# Signals.net
KiCad netlist of a schematic drawn in Altium Designer
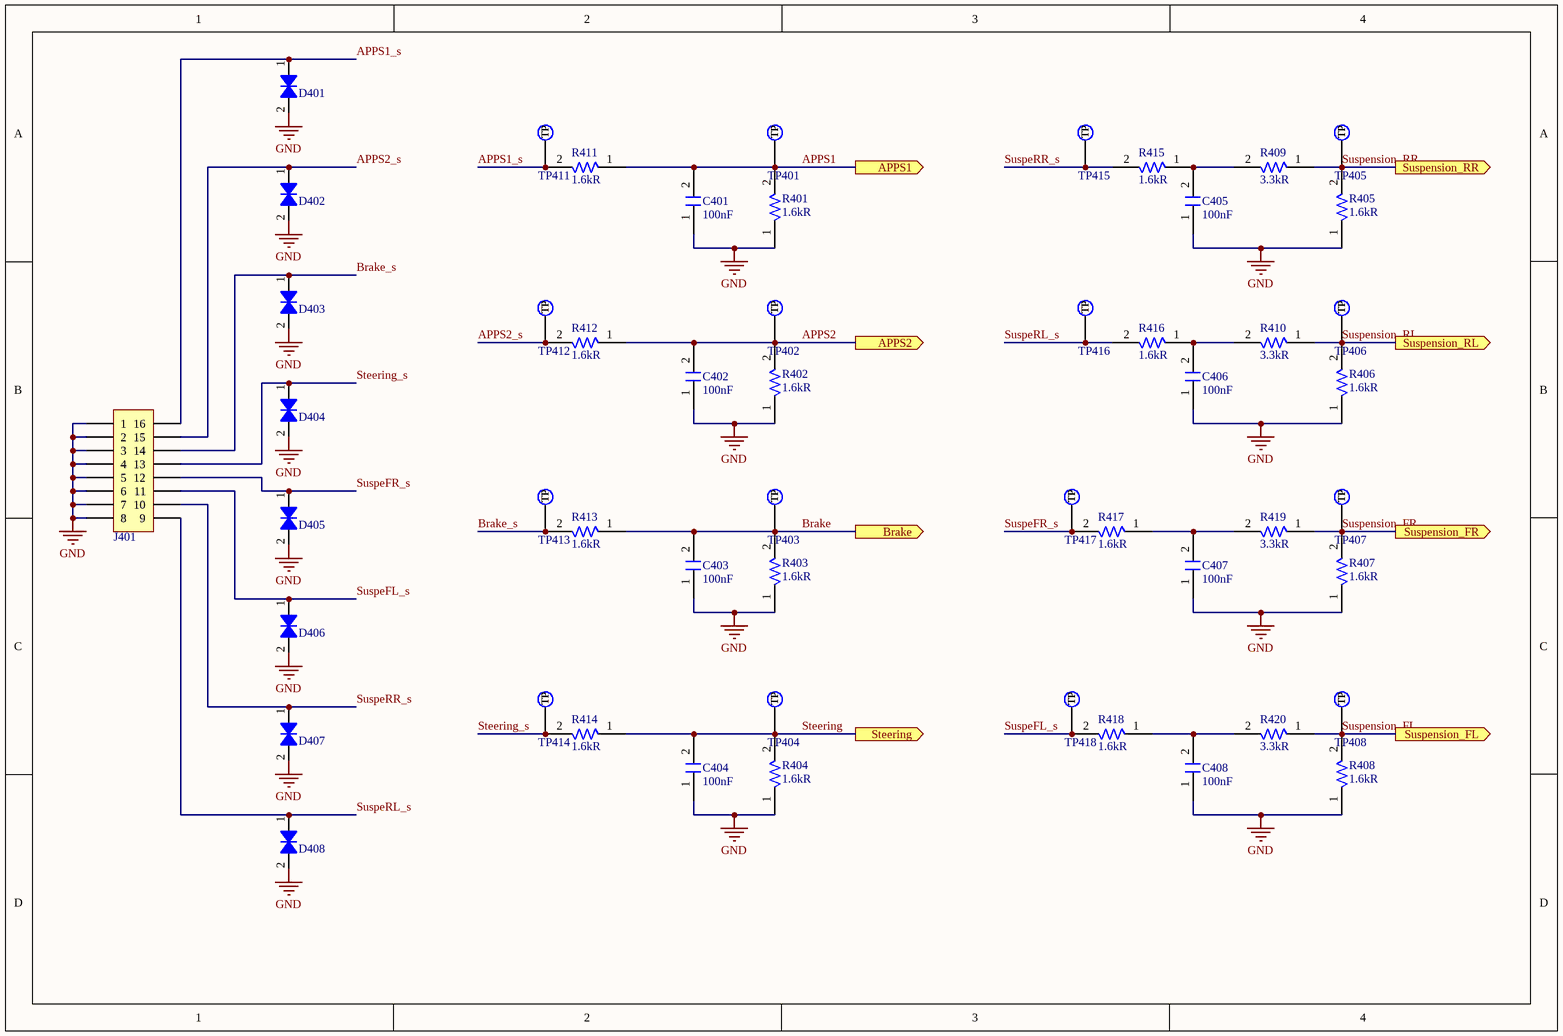
[diagram p0: Signals.SchDoc]

(export (version "E")
  (design (tool "Eeschema 10.0.6"))
  (components
    (comp (ref "C401")
      (value "885012208009")
      (footprint "C1206FNPC-RW")
      (description "Cap, 0.1ΜF, 10V, 10%, X7R, 1206")
      (fields (field (name "TOLERANCE") "10%") (field (name "CAPACITANCE") "100nF"))
      (libsource (lib "Passives") (part "C100n-10V-1206FNPC-X7R"))
    )
    (comp (ref "C402")
      (value "885012208009")
      (footprint "C1206FNPC-RW")
      (description "Cap, 0.1ΜF, 10V, 10%, X7R, 1206")
      (fields (field (name "TOLERANCE") "10%") (field (name "CAPACITANCE") "100nF"))
      (libsource (lib "Passives") (part "C100n-10V-1206FNPC-X7R"))
    )
    (comp (ref "C403")
      (value "885012208009")
      (footprint "C1206FNPC-RW")
      (description "Cap, 0.1ΜF, 10V, 10%, X7R, 1206")
      (fields (field (name "TOLERANCE") "10%") (field (name "CAPACITANCE") "100nF"))
      (libsource (lib "Passives") (part "C100n-10V-1206FNPC-X7R"))
    )
    (comp (ref "C404")
      (value "885012208009")
      (footprint "C1206FNPC-RW")
      (description "Cap, 0.1ΜF, 10V, 10%, X7R, 1206")
      (fields (field (name "TOLERANCE") "10%") (field (name "CAPACITANCE") "100nF"))
      (libsource (lib "Passives") (part "C100n-10V-1206FNPC-X7R"))
    )
    (comp (ref "C405")
      (value "885012208009")
      (footprint "C1206FNPC-RW")
      (description "Cap, 0.1ΜF, 10V, 10%, X7R, 1206")
      (fields (field (name "TOLERANCE") "10%") (field (name "CAPACITANCE") "100nF"))
      (libsource (lib "Passives") (part "C100n-10V-1206FNPC-X7R"))
    )
    (comp (ref "C406")
      (value "885012208009")
      (footprint "C1206FNPC-RW")
      (description "Cap, 0.1ΜF, 10V, 10%, X7R, 1206")
      (fields (field (name "TOLERANCE") "10%") (field (name "CAPACITANCE") "100nF"))
      (libsource (lib "Passives") (part "C100n-10V-1206FNPC-X7R"))
    )
    (comp (ref "C407")
      (value "885012208009")
      (footprint "C1206FNPC-RW")
      (description "Cap, 0.1ΜF, 10V, 10%, X7R, 1206")
      (fields (field (name "TOLERANCE") "10%") (field (name "CAPACITANCE") "100nF"))
      (libsource (lib "Passives") (part "C100n-10V-1206FNPC-X7R"))
    )
    (comp (ref "C408")
      (value "885012208009")
      (footprint "C1206FNPC-RW")
      (description "Cap, 0.1ΜF, 10V, 10%, X7R, 1206")
      (fields (field (name "TOLERANCE") "10%") (field (name "CAPACITANCE") "100nF"))
      (libsource (lib "Passives") (part "C100n-10V-1206FNPC-X7R"))
    )
    (comp (ref "D401")
      (value "824501600")
      (footprint "DTVS-DO-214AC")
      (description "TVS diode [Würth Elektronik] 824501600 TVS diode")
      (fields (field (name "MANUFACTURER") "Wurth Electronics"))
      (libsource (lib "Filter components") (part "DTVS-6V-DO-214AC"))
    )
    (comp (ref "D402")
      (value "824501600")
      (footprint "DTVS-DO-214AC")
      (description "TVS diode [Würth Elektronik] 824501600 TVS diode")
      (fields (field (name "MANUFACTURER") "Wurth Electronics"))
      (libsource (lib "Filter components") (part "DTVS-6V-DO-214AC"))
    )
    (comp (ref "D403")
      (value "824501600")
      (footprint "DTVS-DO-214AC")
      (description "TVS diode [Würth Elektronik] 824501600 TVS diode")
      (fields (field (name "MANUFACTURER") "Wurth Electronics"))
      (libsource (lib "Filter components") (part "DTVS-6V-DO-214AC"))
    )
    (comp (ref "D404")
      (value "824501600")
      (footprint "DTVS-DO-214AC")
      (description "TVS diode [Würth Elektronik] 824501600 TVS diode")
      (fields (field (name "MANUFACTURER") "Wurth Electronics"))
      (libsource (lib "Filter components") (part "DTVS-6V-DO-214AC"))
    )
    (comp (ref "D405")
      (value "824501600")
      (footprint "DTVS-DO-214AC")
      (description "TVS diode [Würth Elektronik] 824501600 TVS diode")
      (fields (field (name "MANUFACTURER") "Wurth Electronics"))
      (libsource (lib "Filter components") (part "DTVS-6V-DO-214AC"))
    )
    (comp (ref "D406")
      (value "824501600")
      (footprint "DTVS-DO-214AC")
      (description "TVS diode [Würth Elektronik] 824501600 TVS diode")
      (fields (field (name "MANUFACTURER") "Wurth Electronics"))
      (libsource (lib "Filter components") (part "DTVS-6V-DO-214AC"))
    )
    (comp (ref "D407")
      (value "824501600")
      (footprint "DTVS-DO-214AC")
      (description "TVS diode [Würth Elektronik] 824501600 TVS diode")
      (fields (field (name "MANUFACTURER") "Wurth Electronics"))
      (libsource (lib "Filter components") (part "DTVS-6V-DO-214AC"))
    )
    (comp (ref "D408")
      (value "824501600")
      (footprint "DTVS-DO-214AC")
      (description "TVS diode [Würth Elektronik] 824501600 TVS diode")
      (fields (field (name "MANUFACTURER") "Wurth Electronics"))
      (libsource (lib "Filter components") (part "DTVS-6V-DO-214AC"))
    )
    (comp (ref "J401")
      (value "1053101116")
      (footprint "J-N2x8_V")
      (libsource (lib "Electromechanical") (part "J_signals2x8_V"))
    )
    (comp (ref "R401")
      (value "CRCW12061K60FKEA")
      (footprint "R1206FTK-W")
      (description "Res Thick Film 1206 1.6K Ohm 1% 1/4W ±100ppm/°C Molded SMD SMD Paper T/R")
      (fields (field (name "TOLERANCE") "1%") (field (name "RESISTANCE") "1.6kR"))
      (libsource (lib "Passives") (part "R1.6K-1206FTK"))
    )
    (comp (ref "R402")
      (value "CRCW12061K60FKEA")
      (footprint "R1206FTK-W")
      (description "Res Thick Film 1206 1.6K Ohm 1% 1/4W ±100ppm/°C Molded SMD SMD Paper T/R")
      (fields (field (name "TOLERANCE") "1%") (field (name "RESISTANCE") "1.6kR"))
      (libsource (lib "Passives") (part "R1.6K-1206FTK"))
    )
    (comp (ref "R403")
      (value "CRCW12061K60FKEA")
      (footprint "R1206FTK-W")
      (description "Res Thick Film 1206 1.6K Ohm 1% 1/4W ±100ppm/°C Molded SMD SMD Paper T/R")
      (fields (field (name "TOLERANCE") "1%") (field (name "RESISTANCE") "1.6kR"))
      (libsource (lib "Passives") (part "R1.6K-1206FTK"))
    )
    (comp (ref "R404")
      (value "CRCW12061K60FKEA")
      (footprint "R1206FTK-W")
      (description "Res Thick Film 1206 1.6K Ohm 1% 1/4W ±100ppm/°C Molded SMD SMD Paper T/R")
      (fields (field (name "TOLERANCE") "1%") (field (name "RESISTANCE") "1.6kR"))
      (libsource (lib "Passives") (part "R1.6K-1206FTK"))
    )
    (comp (ref "R405")
      (value "CRCW12064K30FKEA")
      (footprint "R1206FTK-W")
      (description "Res Thick Film 1206 4.3K Ohm 1% 1/4W ±100ppm/°C Molded SMD SMD Paper T/R")
      (fields (field (name "TOLERANCE") "1%") (field (name "RESISTANCE") "1.6kR"))
      (libsource (lib "Passives") (part "R4.3K-1206FTK"))
    )
    (comp (ref "R406")
      (value "CRCW12064K30FKEA")
      (footprint "R1206FTK-W")
      (description "Res Thick Film 1206 4.3K Ohm 1% 1/4W ±100ppm/°C Molded SMD SMD Paper T/R")
      (fields (field (name "TOLERANCE") "1%") (field (name "RESISTANCE") "1.6kR"))
      (libsource (lib "Passives") (part "R4.3K-1206FTK"))
    )
    (comp (ref "R407")
      (value "CRCW12064K30FKEA")
      (footprint "R1206FTK-W")
      (description "Res Thick Film 1206 4.3K Ohm 1% 1/4W ±100ppm/°C Molded SMD SMD Paper T/R")
      (fields (field (name "TOLERANCE") "1%") (field (name "RESISTANCE") "1.6kR"))
      (libsource (lib "Passives") (part "R4.3K-1206FTK"))
    )
    (comp (ref "R408")
      (value "CRCW12064K30FKEA")
      (footprint "R1206FTK-W")
      (description "Res Thick Film 1206 4.3K Ohm 1% 1/4W ±100ppm/°C Molded SMD SMD Paper T/R")
      (fields (field (name "TOLERANCE") "1%") (field (name "RESISTANCE") "1.6kR"))
      (libsource (lib "Passives") (part "R4.3K-1206FTK"))
    )
    (comp (ref "R409")
      (value "CRCW12066K19FKEA")
      (footprint "R1206FTK-W")
      (description "Res Thick Film 1206 6.19K Ohm 1% 1/4W ±100ppm/°C Molded SMD SMD Paper T/R")
      (fields (field (name "TOLERANCE") "1%") (field (name "RESISTANCE") "3.3kR"))
      (libsource (lib "Passives") (part "R6.2K-1206FTK"))
    )
    (comp (ref "R410")
      (value "CRCW12066K19FKEA")
      (footprint "R1206FTK-W")
      (description "Res Thick Film 1206 6.19K Ohm 1% 1/4W ±100ppm/°C Molded SMD SMD Paper T/R")
      (fields (field (name "TOLERANCE") "1%") (field (name "RESISTANCE") "3.3kR"))
      (libsource (lib "Passives") (part "R6.2K-1206FTK"))
    )
    (comp (ref "R411")
      (value "CRCW12061K60FKEA")
      (footprint "R1206FTK-W")
      (description "Res Thick Film 1206 1.6K Ohm 1% 1/4W ±100ppm/°C Molded SMD SMD Paper T/R")
      (fields (field (name "TOLERANCE") "1%") (field (name "RESISTANCE") "1.6kR"))
      (libsource (lib "Passives") (part "R1.6K-1206FTK"))
    )
    (comp (ref "R412")
      (value "CRCW12061K60FKEA")
      (footprint "R1206FTK-W")
      (description "Res Thick Film 1206 1.6K Ohm 1% 1/4W ±100ppm/°C Molded SMD SMD Paper T/R")
      (fields (field (name "TOLERANCE") "1%") (field (name "RESISTANCE") "1.6kR"))
      (libsource (lib "Passives") (part "R1.6K-1206FTK"))
    )
    (comp (ref "R413")
      (value "CRCW12061K60FKEA")
      (footprint "R1206FTK-W")
      (description "Res Thick Film 1206 1.6K Ohm 1% 1/4W ±100ppm/°C Molded SMD SMD Paper T/R")
      (fields (field (name "TOLERANCE") "1%") (field (name "RESISTANCE") "1.6kR"))
      (libsource (lib "Passives") (part "R1.6K-1206FTK"))
    )
    (comp (ref "R414")
      (value "CRCW12061K60FKEA")
      (footprint "R1206FTK-W")
      (description "Res Thick Film 1206 1.6K Ohm 1% 1/4W ±100ppm/°C Molded SMD SMD Paper T/R")
      (fields (field (name "TOLERANCE") "1%") (field (name "RESISTANCE") "1.6kR"))
      (libsource (lib "Passives") (part "R1.6K-1206FTK"))
    )
    (comp (ref "R415")
      (value "CRCW12061K60FKEA")
      (footprint "R1206FTK-W")
      (description "Res Thick Film 1206 1.6K Ohm 1% 1/4W ±100ppm/°C Molded SMD SMD Paper T/R")
      (fields (field (name "TOLERANCE") "1%") (field (name "RESISTANCE") "1.6kR"))
      (libsource (lib "Passives") (part "R1.6K-1206FTK"))
    )
    (comp (ref "R416")
      (value "CRCW12061K60FKEA")
      (footprint "R1206FTK-W")
      (description "Res Thick Film 1206 1.6K Ohm 1% 1/4W ±100ppm/°C Molded SMD SMD Paper T/R")
      (fields (field (name "TOLERANCE") "1%") (field (name "RESISTANCE") "1.6kR"))
      (libsource (lib "Passives") (part "R1.6K-1206FTK"))
    )
    (comp (ref "R417")
      (value "CRCW12061K60FKEA")
      (footprint "R1206FTK-W")
      (description "Res Thick Film 1206 1.6K Ohm 1% 1/4W ±100ppm/°C Molded SMD SMD Paper T/R")
      (fields (field (name "TOLERANCE") "1%") (field (name "RESISTANCE") "1.6kR"))
      (libsource (lib "Passives") (part "R1.6K-1206FTK"))
    )
    (comp (ref "R418")
      (value "CRCW12061K60FKEA")
      (footprint "R1206FTK-W")
      (description "Res Thick Film 1206 1.6K Ohm 1% 1/4W ±100ppm/°C Molded SMD SMD Paper T/R")
      (fields (field (name "TOLERANCE") "1%") (field (name "RESISTANCE") "1.6kR"))
      (libsource (lib "Passives") (part "R1.6K-1206FTK"))
    )
    (comp (ref "R419")
      (value "CRCW12066K19FKEA")
      (footprint "R1206FTK-W")
      (description "Res Thick Film 1206 6.19K Ohm 1% 1/4W ±100ppm/°C Molded SMD SMD Paper T/R")
      (fields (field (name "TOLERANCE") "1%") (field (name "RESISTANCE") "3.3kR"))
      (libsource (lib "Passives") (part "R6.2K-1206FTK"))
    )
    (comp (ref "R420")
      (value "CRCW12066K19FKEA")
      (footprint "R1206FTK-W")
      (description "Res Thick Film 1206 6.19K Ohm 1% 1/4W ±100ppm/°C Molded SMD SMD Paper T/R")
      (fields (field (name "TOLERANCE") "1%") (field (name "RESISTANCE") "3.3kR"))
      (libsource (lib "Passives") (part "R6.2K-1206FTK"))
    )
    (comp (ref "TP401")
      (value "TestPoint")
      (footprint "TestPoint")
      (description "Test Point 1x1 mm")
      (libsource (lib "e-Tech_Racing") (part "TestPoint"))
    )
    (comp (ref "TP402")
      (value "TestPoint")
      (footprint "TestPoint")
      (description "Test Point 1x1 mm")
      (libsource (lib "e-Tech_Racing") (part "TestPoint"))
    )
    (comp (ref "TP403")
      (value "TestPoint")
      (footprint "TestPoint")
      (description "Test Point 1x1 mm")
      (libsource (lib "e-Tech_Racing") (part "TestPoint"))
    )
    (comp (ref "TP404")
      (value "TestPoint")
      (footprint "TestPoint")
      (description "Test Point 1x1 mm")
      (libsource (lib "e-Tech_Racing") (part "TestPoint"))
    )
    (comp (ref "TP405")
      (value "TestPoint")
      (footprint "TestPoint")
      (description "Test Point 1x1 mm")
      (libsource (lib "e-Tech_Racing") (part "TestPoint"))
    )
    (comp (ref "TP406")
      (value "TestPoint")
      (footprint "TestPoint")
      (description "Test Point 1x1 mm")
      (libsource (lib "e-Tech_Racing") (part "TestPoint"))
    )
    (comp (ref "TP407")
      (value "TestPoint")
      (footprint "TestPoint")
      (description "Test Point 1x1 mm")
      (libsource (lib "e-Tech_Racing") (part "TestPoint"))
    )
    (comp (ref "TP408")
      (value "TestPoint")
      (footprint "TestPoint")
      (description "Test Point 1x1 mm")
      (libsource (lib "e-Tech_Racing") (part "TestPoint"))
    )
    (comp (ref "TP411")
      (value "TestPoint")
      (footprint "TestPoint")
      (description "Test Point 1x1 mm")
      (libsource (lib "e-Tech_Racing") (part "TestPoint"))
    )
    (comp (ref "TP412")
      (value "TestPoint")
      (footprint "TestPoint")
      (description "Test Point 1x1 mm")
      (libsource (lib "e-Tech_Racing") (part "TestPoint"))
    )
    (comp (ref "TP413")
      (value "TestPoint")
      (footprint "TestPoint")
      (description "Test Point 1x1 mm")
      (libsource (lib "e-Tech_Racing") (part "TestPoint"))
    )
    (comp (ref "TP414")
      (value "TestPoint")
      (footprint "TestPoint")
      (description "Test Point 1x1 mm")
      (libsource (lib "e-Tech_Racing") (part "TestPoint"))
    )
    (comp (ref "TP415")
      (value "TestPoint")
      (footprint "TestPoint")
      (description "Test Point 1x1 mm")
      (libsource (lib "e-Tech_Racing") (part "TestPoint"))
    )
    (comp (ref "TP416")
      (value "TestPoint")
      (footprint "TestPoint")
      (description "Test Point 1x1 mm")
      (libsource (lib "e-Tech_Racing") (part "TestPoint"))
    )
    (comp (ref "TP417")
      (value "TestPoint")
      (footprint "TestPoint")
      (description "Test Point 1x1 mm")
      (libsource (lib "e-Tech_Racing") (part "TestPoint"))
    )
    (comp (ref "TP418")
      (value "TestPoint")
      (footprint "TestPoint")
      (description "Test Point 1x1 mm")
      (libsource (lib "e-Tech_Racing") (part "TestPoint"))
    )
  )
  (nets
    (net (code "1") (name "/APPS1") (class "Default")
      (node (ref "C401") (pin "2") (pinfunction "2_2") (pintype "passive"))
      (node (ref "R401") (pin "2") (pinfunction "2_2") (pintype "passive"))
      (node (ref "R411") (pin "1") (pinfunction "1_1") (pintype "passive"))
      (node (ref "TP401") (pin "1") (pinfunction "TP_1") (pintype "passive"))
    )
    (net (code "2") (name "/APPS1_s") (class "Default")
      (node (ref "D401") (pin "1") (pinfunction "1_1") (pintype "passive"))
      (node (ref "J401") (pin "16") (pinfunction "16_16") (pintype "passive"))
      (node (ref "R411") (pin "2") (pinfunction "2_2") (pintype "passive"))
      (node (ref "TP411") (pin "1") (pinfunction "TP_1") (pintype "passive"))
    )
    (net (code "3") (name "/APPS2") (class "Default")
      (node (ref "C402") (pin "2") (pinfunction "2_2") (pintype "passive"))
      (node (ref "R402") (pin "2") (pinfunction "2_2") (pintype "passive"))
      (node (ref "R412") (pin "1") (pinfunction "1_1") (pintype "passive"))
      (node (ref "TP402") (pin "1") (pinfunction "TP_1") (pintype "passive"))
    )
    (net (code "4") (name "/APPS2_s") (class "Default")
      (node (ref "D402") (pin "1") (pinfunction "1_1") (pintype "passive"))
      (node (ref "J401") (pin "15") (pinfunction "15_15") (pintype "passive"))
      (node (ref "R412") (pin "2") (pinfunction "2_2") (pintype "passive"))
      (node (ref "TP412") (pin "1") (pinfunction "TP_1") (pintype "passive"))
    )
    (net (code "5") (name "/Brake") (class "Default")
      (node (ref "C403") (pin "2") (pinfunction "2_2") (pintype "passive"))
      (node (ref "R403") (pin "2") (pinfunction "2_2") (pintype "passive"))
      (node (ref "R413") (pin "1") (pinfunction "1_1") (pintype "passive"))
      (node (ref "TP403") (pin "1") (pinfunction "TP_1") (pintype "passive"))
    )
    (net (code "6") (name "/Brake_s") (class "Default")
      (node (ref "D403") (pin "1") (pinfunction "1_1") (pintype "passive"))
      (node (ref "J401") (pin "14") (pinfunction "14_14") (pintype "passive"))
      (node (ref "R413") (pin "2") (pinfunction "2_2") (pintype "passive"))
      (node (ref "TP413") (pin "1") (pinfunction "TP_1") (pintype "passive"))
    )
    (net (code "7") (name "/Steering") (class "Default")
      (node (ref "C404") (pin "2") (pinfunction "2_2") (pintype "passive"))
      (node (ref "R404") (pin "2") (pinfunction "2_2") (pintype "passive"))
      (node (ref "R414") (pin "1") (pinfunction "1_1") (pintype "passive"))
      (node (ref "TP404") (pin "1") (pinfunction "TP_1") (pintype "passive"))
    )
    (net (code "8") (name "/Steering_s") (class "Default")
      (node (ref "D404") (pin "1") (pinfunction "1_1") (pintype "passive"))
      (node (ref "J401") (pin "13") (pinfunction "13_13") (pintype "passive"))
      (node (ref "R414") (pin "2") (pinfunction "2_2") (pintype "passive"))
      (node (ref "TP414") (pin "1") (pinfunction "TP_1") (pintype "passive"))
    )
    (net (code "9") (name "/SuspeFL_s") (class "Default")
      (node (ref "D406") (pin "1") (pinfunction "1_1") (pintype "passive"))
      (node (ref "J401") (pin "11") (pinfunction "11_11") (pintype "passive"))
      (node (ref "R418") (pin "2") (pinfunction "2_2") (pintype "passive"))
      (node (ref "TP418") (pin "1") (pinfunction "TP_1") (pintype "passive"))
    )
    (net (code "10") (name "/SuspeFR_s") (class "Default")
      (node (ref "D405") (pin "1") (pinfunction "1_1") (pintype "passive"))
      (node (ref "J401") (pin "12") (pinfunction "12_12") (pintype "passive"))
      (node (ref "R417") (pin "2") (pinfunction "2_2") (pintype "passive"))
      (node (ref "TP417") (pin "1") (pinfunction "TP_1") (pintype "passive"))
    )
    (net (code "11") (name "/SuspeRL_s") (class "Default")
      (node (ref "D408") (pin "1") (pinfunction "1_1") (pintype "passive"))
      (node (ref "J401") (pin "9") (pinfunction "9_9") (pintype "passive"))
      (node (ref "R416") (pin "2") (pinfunction "2_2") (pintype "passive"))
      (node (ref "TP416") (pin "1") (pinfunction "TP_1") (pintype "passive"))
    )
    (net (code "12") (name "/SuspeRR_s") (class "Default")
      (node (ref "D407") (pin "1") (pinfunction "1_1") (pintype "passive"))
      (node (ref "J401") (pin "10") (pinfunction "10_10") (pintype "passive"))
      (node (ref "R415") (pin "2") (pinfunction "2_2") (pintype "passive"))
      (node (ref "TP415") (pin "1") (pinfunction "TP_1") (pintype "passive"))
    )
    (net (code "13") (name "/Suspension_FL") (class "Default")
      (node (ref "R408") (pin "2") (pinfunction "2_2") (pintype "passive"))
      (node (ref "R420") (pin "1") (pinfunction "1_1") (pintype "passive"))
      (node (ref "TP408") (pin "1") (pinfunction "TP_1") (pintype "passive"))
    )
    (net (code "14") (name "/Suspension_FR") (class "Default")
      (node (ref "R407") (pin "2") (pinfunction "2_2") (pintype "passive"))
      (node (ref "R419") (pin "1") (pinfunction "1_1") (pintype "passive"))
      (node (ref "TP407") (pin "1") (pinfunction "TP_1") (pintype "passive"))
    )
    (net (code "15") (name "/Suspension_RL") (class "Default")
      (node (ref "R406") (pin "2") (pinfunction "2_2") (pintype "passive"))
      (node (ref "R410") (pin "1") (pinfunction "1_1") (pintype "passive"))
      (node (ref "TP406") (pin "1") (pinfunction "TP_1") (pintype "passive"))
    )
    (net (code "16") (name "/Suspension_RR") (class "Default")
      (node (ref "R405") (pin "2") (pinfunction "2_2") (pintype "passive"))
      (node (ref "R409") (pin "1") (pinfunction "1_1") (pintype "passive"))
      (node (ref "TP405") (pin "1") (pinfunction "TP_1") (pintype "passive"))
    )
    (net (code "17") (name "GND") (class "Default")
      (node (ref "C401") (pin "1") (pinfunction "1_1") (pintype "passive"))
      (node (ref "C402") (pin "1") (pinfunction "1_1") (pintype "passive"))
      (node (ref "C403") (pin "1") (pinfunction "1_1") (pintype "passive"))
      (node (ref "C404") (pin "1") (pinfunction "1_1") (pintype "passive"))
      (node (ref "C405") (pin "1") (pinfunction "1_1") (pintype "passive"))
      (node (ref "C406") (pin "1") (pinfunction "1_1") (pintype "passive"))
      (node (ref "C407") (pin "1") (pinfunction "1_1") (pintype "passive"))
      (node (ref "C408") (pin "1") (pinfunction "1_1") (pintype "passive"))
      (node (ref "D401") (pin "2") (pinfunction "2_2") (pintype "passive"))
      (node (ref "D402") (pin "2") (pinfunction "2_2") (pintype "passive"))
      (node (ref "D403") (pin "2") (pinfunction "2_2") (pintype "passive"))
      (node (ref "D404") (pin "2") (pinfunction "2_2") (pintype "passive"))
      (node (ref "D405") (pin "2") (pinfunction "2_2") (pintype "passive"))
      (node (ref "D406") (pin "2") (pinfunction "2_2") (pintype "passive"))
      (node (ref "D407") (pin "2") (pinfunction "2_2") (pintype "passive"))
      (node (ref "D408") (pin "2") (pinfunction "2_2") (pintype "passive"))
      (node (ref "J401") (pin "1") (pinfunction "1_1") (pintype "passive"))
      (node (ref "J401") (pin "2") (pinfunction "2_2") (pintype "passive"))
      (node (ref "J401") (pin "3") (pinfunction "3_3") (pintype "passive"))
      (node (ref "J401") (pin "4") (pinfunction "4_4") (pintype "passive"))
      (node (ref "J401") (pin "5") (pinfunction "5_5") (pintype "passive"))
      (node (ref "J401") (pin "6") (pinfunction "6_6") (pintype "passive"))
      (node (ref "J401") (pin "7") (pinfunction "7_7") (pintype "passive"))
      (node (ref "J401") (pin "8") (pinfunction "8_8") (pintype "passive"))
      (node (ref "R401") (pin "1") (pinfunction "1_1") (pintype "passive"))
      (node (ref "R402") (pin "1") (pinfunction "1_1") (pintype "passive"))
      (node (ref "R403") (pin "1") (pinfunction "1_1") (pintype "passive"))
      (node (ref "R404") (pin "1") (pinfunction "1_1") (pintype "passive"))
      (node (ref "R405") (pin "1") (pinfunction "1_1") (pintype "passive"))
      (node (ref "R406") (pin "1") (pinfunction "1_1") (pintype "passive"))
      (node (ref "R407") (pin "1") (pinfunction "1_1") (pintype "passive"))
      (node (ref "R408") (pin "1") (pinfunction "1_1") (pintype "passive"))
    )
    (net (code "18") (name "Net-(C405-Pad2)") (class "Default")
      (node (ref "C405") (pin "2") (pinfunction "2_2") (pintype "passive"))
      (node (ref "R409") (pin "2") (pinfunction "2_2") (pintype "passive"))
      (node (ref "R415") (pin "1") (pinfunction "1_1") (pintype "passive"))
    )
    (net (code "19") (name "Net-(C406-Pad2)") (class "Default")
      (node (ref "C406") (pin "2") (pinfunction "2_2") (pintype "passive"))
      (node (ref "R410") (pin "2") (pinfunction "2_2") (pintype "passive"))
      (node (ref "R416") (pin "1") (pinfunction "1_1") (pintype "passive"))
    )
    (net (code "20") (name "Net-(C407-Pad2)") (class "Default")
      (node (ref "C407") (pin "2") (pinfunction "2_2") (pintype "passive"))
      (node (ref "R417") (pin "1") (pinfunction "1_1") (pintype "passive"))
      (node (ref "R419") (pin "2") (pinfunction "2_2") (pintype "passive"))
    )
    (net (code "21") (name "Net-(C408-Pad2)") (class "Default")
      (node (ref "C408") (pin "2") (pinfunction "2_2") (pintype "passive"))
      (node (ref "R418") (pin "1") (pinfunction "1_1") (pintype "passive"))
      (node (ref "R420") (pin "2") (pinfunction "2_2") (pintype "passive"))
    )
  )
)
